# Tesla_Coil_Schematic.net
KiCad netlist of a schematic drawn in Altium Designer
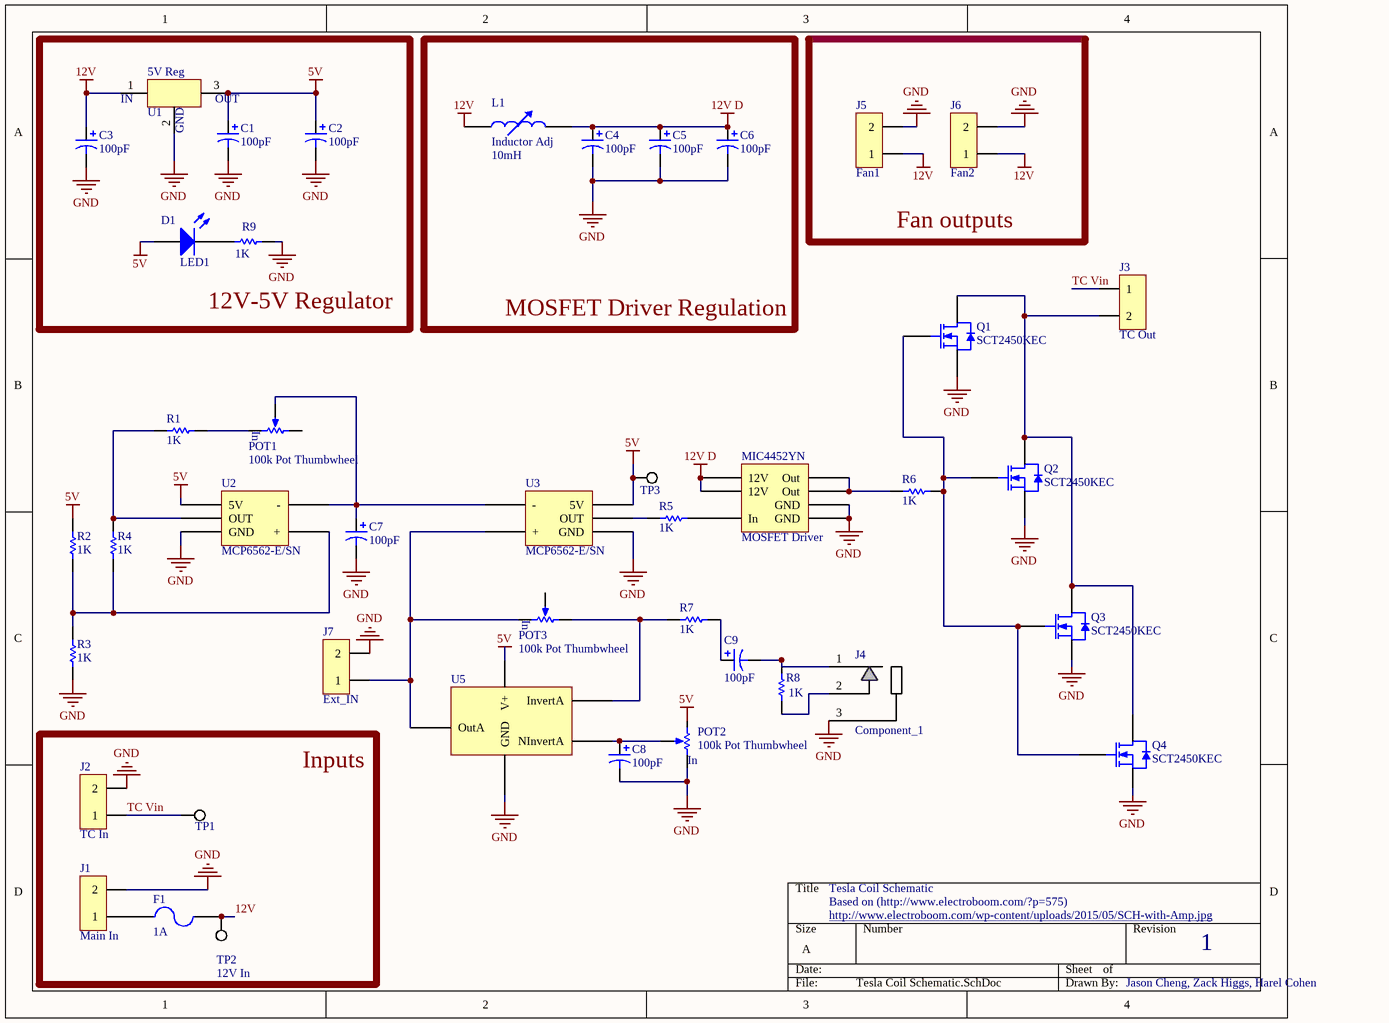
[diagram p0: Tesla Coil Schematic.SchDoc]

(export (version "E")
  (design (tool "Eeschema 10.0.6"))
  (components
    (comp (ref "C1")
      (value "100pF")
      (footprint "CAPPR5-10X30")
      (description "Cap, Gen, 5-10x30")
      (fields (field (name "Comment") "Cap 5-10x30") (field (name "PUBLISHER") "Altium Limited"))
      (libsource (lib "Common") (part "Cap 5-10x30"))
    )
    (comp (ref "C2")
      (value "100pF")
      (footprint "CAPPR5-10X30")
      (description "Cap, Gen, 5-10x30")
      (fields (field (name "Comment") "Cap 5-10x30") (field (name "PUBLISHER") "Altium Limited"))
      (libsource (lib "Common") (part "Cap 5-10x30"))
    )
    (comp (ref "C3")
      (value "100pF")
      (footprint "CAPPR5-10X30")
      (description "Cap, Gen, 5-10x30")
      (fields (field (name "Comment") "Cap 5-10x30") (field (name "PUBLISHER") "Altium Limited"))
      (libsource (lib "Common") (part "Cap 5-10x30"))
    )
    (comp (ref "C4")
      (value "100pF")
      (footprint "CAPPR5-10X30")
      (description "Cap, Gen, 5-10x30")
      (fields (field (name "Comment") "Cap 5-10x30") (field (name "PUBLISHER") "Altium Limited"))
      (libsource (lib "Common") (part "Cap 5-10x30"))
    )
    (comp (ref "C5")
      (value "100pF")
      (footprint "CAPPR5-10X30")
      (description "Cap, Gen, 5-10x30")
      (fields (field (name "Comment") "Cap 5-10x30") (field (name "PUBLISHER") "Altium Limited"))
      (libsource (lib "Common") (part "Cap 5-10x30"))
    )
    (comp (ref "C6")
      (value "100pF")
      (footprint "CAPPR5-10X30")
      (description "Cap, Gen, 5-10x30")
      (fields (field (name "Comment") "Cap 5-10x30") (field (name "PUBLISHER") "Altium Limited"))
      (libsource (lib "Common") (part "Cap 5-10x30"))
    )
    (comp (ref "C7")
      (value "100pF")
      (footprint "CAPPR2-5X11")
      (description "Cap, Gen, 2-5x11")
      (fields (field (name "Comment") "Cap 2-5x11") (field (name "PUBLISHER") "Altium Limited"))
      (libsource (lib "Common") (part "Cap 2-5x11"))
    )
    (comp (ref "C8")
      (value "100pF")
      (footprint "CAPPR2-5X11")
      (description "Cap, Gen, 2-5x11")
      (fields (field (name "Comment") "Cap 2-5x11") (field (name "PUBLISHER") "Altium Limited"))
      (libsource (lib "Common") (part "Cap 2-5x11"))
    )
    (comp (ref "C9")
      (value "100pF")
      (footprint "CAPPR5-10X30")
      (description "Cap, Gen, 5-10x30")
      (fields (field (name "Comment") "Cap 5-10x30") (field (name "PUBLISHER") "Altium Limited"))
      (libsource (lib "Common") (part "Cap 5-10x30"))
    )
    (comp (ref "D1")
      (value "LED1")
      (footprint "LED-1")
      (description "Typical RED GaAs LED")
      (fields (field (name "PUBLISHER") "Altium Limited"))
      (libsource (lib "Miscellaneous Devices") (part "LED1"))
    )
    (comp (ref "F1")
      (value "1A")
      (footprint "Dabs PCB file (1):Blade Fuse")
      (description "Fuse")
      (fields (field (name "PUBLISHER") "Altium Limited"))
      (libsource (lib "Dabs PCB project") (part "Fuse 2"))
    )
    (comp (ref "J1")
      (value "Main In")
      (footprint "Dabs PCB file (1):Mini-Fit Jr. 2")
      (description "Mini-Fit Jr. 2-pin Right Angle")
      (fields
        (field (name "MANUFACTURER") "Molex Inc")
        (field (name "MANUFACTURER PART NUMBER") "0039300020")
      )
      (libsource (lib "Dabs PCB project") (part "Mini-Fit Jr. 2-pin"))
    )
    (comp (ref "J2")
      (value "TC In")
      (footprint "Dabs PCB file (1):Mini-Fit Jr. 2")
      (description "Mini-Fit Jr. 2-pin Right Angle")
      (fields
        (field (name "MANUFACTURER") "Molex Inc")
        (field (name "MANUFACTURER PART NUMBER") "0039300020")
      )
      (libsource (lib "Dabs PCB project") (part "Mini-Fit Jr. 2-pin"))
    )
    (comp (ref "J3")
      (value "TC Out")
      (footprint "Dabs PCB file (1):Mini-Fit Jr. 2")
      (description "Mini-Fit Jr. 2-pin Right Angle")
      (fields
        (field (name "MANUFACTURER") "Molex Inc")
        (field (name "MANUFACTURER PART NUMBER") "0039300020")
      )
      (libsource (lib "") (part "Mini-Fit Jr. 2-pin_1"))
    )
    (comp (ref "J4")
      (value "Component_1")
      (footprint "3.5mm HPJ PCB foot:3.5Jack Foot")
      (libsource (lib "3.5mm HPJ TC") (part "Component_1"))
    )
    (comp (ref "J5")
      (value "Fan1")
      (footprint "Dabs PCB file (1):Mini-Fit Jr. 2")
      (description "Mini-Fit Jr. 2-pin Right Angle")
      (fields
        (field (name "MANUFACTURER") "Molex Inc")
        (field (name "MANUFACTURER PART NUMBER") "0039300020")
      )
      (libsource (lib "Dabs PCB project") (part "Mini-Fit Jr. 2-pin"))
    )
    (comp (ref "J6")
      (value "Fan2")
      (footprint "Dabs PCB file (1):Mini-Fit Jr. 2")
      (description "Mini-Fit Jr. 2-pin Right Angle")
      (fields
        (field (name "MANUFACTURER") "Molex Inc")
        (field (name "MANUFACTURER PART NUMBER") "0039300020")
      )
      (libsource (lib "Dabs PCB project") (part "Mini-Fit Jr. 2-pin"))
    )
    (comp (ref "J7")
      (value "Ext_IN")
      (footprint "Dabs PCB file (1):Mini-Fit Jr. 2")
      (description "Mini-Fit Jr. 2-pin Right Angle")
      (fields
        (field (name "MANUFACTURER") "Molex Inc")
        (field (name "MANUFACTURER PART NUMBER") "0039300020")
      )
      (libsource (lib "Dabs PCB project") (part "Mini-Fit Jr. 2-pin"))
    )
    (comp (ref "L1")
      (value "Inductor Adj")
      (footprint "AXIAL-0.8")
      (description "Adjustable Inductor")
      (fields (field (name "ALTIUM_VALUE") "10mH") (field (name "PUBLISHER") "Altium Limited"))
      (libsource (lib "Miscellaneous Devices") (part "Inductor Adj"))
    )
    (comp (ref "MIC4452YN")
      (value "MOSFET Driver")
      (footprint "MIC441/44")
      (libsource (lib "Tesla_Coil_Parts2") (part "MOSFET Driver"))
    )
    (comp (ref "POT1")
      (value "100k Pot Thumbwheel")
      (footprint "10K Pot 3352T")
      (libsource (lib "Tesla_Coil_Parts2") (part "100k Pot Thumbwheel"))
    )
    (comp (ref "POT2")
      (value "100k Pot Thumbwheel")
      (footprint "10K Pot 3352T")
      (libsource (lib "Tesla_Coil_Parts2") (part "100k Pot Thumbwheel"))
    )
    (comp (ref "POT3")
      (value "100k Pot Thumbwheel")
      (footprint "10K Pot 3352T")
      (libsource (lib "Tesla_Coil_Parts2") (part "100k Pot Thumbwheel"))
    )
    (comp (ref "Q1")
      (value "SCT2450KEC")
      (footprint "SCT2450KEC")
      (libsource (lib "Tesla_Coil_Parts2") (part "SCT2450KEC"))
    )
    (comp (ref "Q2")
      (value "SCT2450KEC")
      (footprint "SCT2450KEC")
      (libsource (lib "Tesla_Coil_Parts2") (part "SCT2450KEC"))
    )
    (comp (ref "Q3")
      (value "SCT2450KEC")
      (footprint "SCT2450KEC")
      (libsource (lib "Tesla_Coil_Parts2") (part "SCT2450KEC"))
    )
    (comp (ref "Q4")
      (value "SCT2450KEC")
      (footprint "SCT2450KEC")
      (libsource (lib "Tesla_Coil_Parts2") (part "SCT2450KEC"))
    )
    (comp (ref "R1")
      (value "1K")
      (footprint "RES10.55-7X2.8")
      (description "R, Gen, Thru Hole")
      (fields (field (name "Comment") "R Thru Hole") (field (name "PUBLISHER") "Altium Limited"))
      (libsource (lib "Common") (part "R Thru Hole"))
    )
    (comp (ref "R2")
      (value "1K")
      (footprint "RES10.55-7X2.8")
      (description "R, Gen, Thru Hole")
      (fields (field (name "Comment") "R Thru Hole") (field (name "PUBLISHER") "Altium Limited"))
      (libsource (lib "Common") (part "R Thru Hole"))
    )
    (comp (ref "R3")
      (value "1K")
      (footprint "RES10.55-7X2.8")
      (description "R, Gen, Thru Hole")
      (fields (field (name "Comment") "R Thru Hole") (field (name "PUBLISHER") "Altium Limited"))
      (libsource (lib "Common") (part "R Thru Hole"))
    )
    (comp (ref "R4")
      (value "1K")
      (footprint "RES10.55-7X2.8")
      (description "R, Gen, Thru Hole")
      (fields (field (name "Comment") "R Thru Hole") (field (name "PUBLISHER") "Altium Limited"))
      (libsource (lib "Common") (part "R Thru Hole"))
    )
    (comp (ref "R5")
      (value "1K")
      (footprint "RES10.55-7X2.8")
      (description "R, Gen, Thru Hole")
      (fields (field (name "Comment") "R Thru Hole") (field (name "PUBLISHER") "Altium Limited"))
      (libsource (lib "Common") (part "R Thru Hole"))
    )
    (comp (ref "R6")
      (value "1K")
      (footprint "RES10.55-7X2.8")
      (description "R, Gen, Thru Hole")
      (fields (field (name "Comment") "R Thru Hole") (field (name "PUBLISHER") "Altium Limited"))
      (libsource (lib "Common") (part "R Thru Hole"))
    )
    (comp (ref "R7")
      (value "1K")
      (footprint "RES10.55-7X2.8")
      (description "R, Gen, Thru Hole")
      (fields (field (name "Comment") "R Thru Hole") (field (name "PUBLISHER") "Altium Limited"))
      (libsource (lib "Common") (part "R Thru Hole"))
    )
    (comp (ref "R8")
      (value "1K")
      (footprint "RES10.55-7X2.8")
      (description "R, Gen, Thru Hole")
      (fields (field (name "Comment") "R Thru Hole") (field (name "PUBLISHER") "Altium Limited"))
      (libsource (lib "Common") (part "R Thru Hole"))
    )
    (comp (ref "R9")
      (value "1K")
      (footprint "RES10.55-7X2.8")
      (description "R, Gen, Thru Hole")
      (fields (field (name "Comment") "R Thru Hole") (field (name "PUBLISHER") "Altium Limited"))
      (libsource (lib "Common") (part "R Thru Hole"))
    )
    (comp (ref "TP1")
      (value "Test Point")
      (footprint "Dabs PCB file (1):Test Point")
      (libsource (lib "Dabs PCB project") (part "Test Point"))
    )
    (comp (ref "TP2")
      (value "Test Point")
      (footprint "Dabs PCB file (1):Test Point")
      (fields (field (name "LABEL") "12V In"))
      (libsource (lib "Dabs PCB project") (part "Test Point"))
    )
    (comp (ref "TP3")
      (value "Test Point")
      (footprint "Dabs PCB file (1):Test Point")
      (libsource (lib "Dabs PCB project") (part "Test Point"))
    )
    (comp (ref "U1") (value "REG") (footprint "5V REG") (libsource (lib "Tesla_Coil_Parts2") (part "REG")))
    (comp (ref "U2")
      (value "MCP6562-E/SN")
      (footprint "MCP6562")
      (libsource (lib "Tesla_Coil_Parts") (part "MCP6562-E/SN"))
    )
    (comp (ref "U3")
      (value "MCP6562-E/SN")
      (footprint "MCP6562")
      (libsource (lib "Tesla_Coil_Parts2") (part "MCP6562-E/SN"))
    )
    (comp (ref "U5")
      (value "LM358 (DIP Socket)")
      (footprint "3M5473-ND-")
      (libsource (lib "Tesla_Coil_Parts2") (part "LM358 (DIP Socket)"))
    )
  )
  (nets
    (net (code "1") (name "/TC Vin") (class "Default")
      (node (ref "J2") (pin "1") (pinfunction "1_1") (pintype "passive"))
      (node (ref "J3") (pin "1") (pinfunction "1_1") (pintype "passive"))
      (node (ref "TP1") (pin "1") (pinfunction "1_1") (pintype "passive"))
    )
    (net (code "2") (name "5V") (class "Default")
      (node (ref "C1") (pin "1") (pinfunction "1_1") (pintype "passive"))
      (node (ref "C2") (pin "1") (pinfunction "1_1") (pintype "passive"))
      (node (ref "D1") (pin "1") (pinfunction "A_1") (pintype "passive"))
      (node (ref "R2") (pin "2") (pinfunction "2_2") (pintype "passive"))
      (node (ref "TP3") (pin "1") (pinfunction "1_1") (pintype "passive"))
      (node (ref "U1") (pin "3") (pintype "passive"))
      (node (ref "U2") (pin "5") (pinfunction "5V_5") (pintype "passive"))
      (node (ref "U3") (pin "8") (pinfunction "5V_8") (pintype "passive"))
      (node (ref "U5") (pin "8") (pinfunction "V+_8") (pintype "passive"))
    )
    (net (code "3") (name "12V") (class "Default")
      (node (ref "C3") (pin "1") (pinfunction "1_1") (pintype "passive"))
      (node (ref "F1") (pin "2") (pinfunction "2_2") (pintype "passive"))
      (node (ref "J5") (pin "1") (pinfunction "1_1") (pintype "passive"))
      (node (ref "J6") (pin "1") (pinfunction "1_1") (pintype "passive"))
      (node (ref "L1") (pin "1") (pinfunction "1_1") (pintype "passive"))
      (node (ref "TP2") (pin "1") (pinfunction "1_1") (pintype "passive"))
      (node (ref "U1") (pin "1") (pintype "passive"))
    )
    (net (code "4") (name "12V D") (class "Default")
      (node (ref "C4") (pin "1") (pinfunction "1_1") (pintype "passive"))
      (node (ref "C5") (pin "1") (pinfunction "1_1") (pintype "passive"))
      (node (ref "C6") (pin "1") (pinfunction "1_1") (pintype "passive"))
      (node (ref "L1") (pin "2") (pinfunction "2_2") (pintype "passive"))
      (node (ref "MIC4452YN") (pin "1") (pinfunction "12V_1") (pintype "passive"))
      (node (ref "MIC4452YN") (pin "8") (pinfunction "12V_8") (pintype "passive"))
    )
    (net (code "5") (name "GND") (class "Default")
      (node (ref "C1") (pin "2") (pinfunction "2_2") (pintype "passive"))
      (node (ref "C2") (pin "2") (pinfunction "2_2") (pintype "passive"))
      (node (ref "C3") (pin "2") (pinfunction "2_2") (pintype "passive"))
      (node (ref "C4") (pin "2") (pinfunction "2_2") (pintype "passive"))
      (node (ref "C5") (pin "2") (pinfunction "2_2") (pintype "passive"))
      (node (ref "C6") (pin "2") (pinfunction "2_2") (pintype "passive"))
      (node (ref "C7") (pin "2") (pinfunction "2_2") (pintype "passive"))
      (node (ref "C8") (pin "2") (pinfunction "2_2") (pintype "passive"))
      (node (ref "J1") (pin "2") (pinfunction "2_2") (pintype "passive"))
      (node (ref "J2") (pin "2") (pinfunction "2_2") (pintype "passive"))
      (node (ref "J4") (pin "3") (pinfunction "3_3") (pintype "passive"))
      (node (ref "J5") (pin "2") (pinfunction "2_2") (pintype "passive"))
      (node (ref "J6") (pin "2") (pinfunction "2_2") (pintype "passive"))
      (node (ref "J7") (pin "2") (pinfunction "2_2") (pintype "passive"))
      (node (ref "MIC4452YN") (pin "5") (pinfunction "GND_5") (pintype "passive"))
      (node (ref "MIC4452YN") (pin "6") (pinfunction "GND_6") (pintype "passive"))
      (node (ref "POT2") (pin "1") (pinfunction "In_1") (pintype "passive"))
      (node (ref "Q1") (pin "3") (pinfunction "3_3") (pintype "passive"))
      (node (ref "Q2") (pin "3") (pinfunction "3_3") (pintype "passive"))
      (node (ref "Q3") (pin "3") (pinfunction "3_3") (pintype "passive"))
      (node (ref "Q4") (pin "3") (pinfunction "3_3") (pintype "passive"))
      (node (ref "R3") (pin "1") (pinfunction "1_1") (pintype "passive"))
      (node (ref "R9") (pin "1") (pinfunction "1_1") (pintype "passive"))
      (node (ref "U1") (pin "2") (pintype "passive"))
      (node (ref "U2") (pin "2") (pinfunction "GND_2") (pintype "passive"))
      (node (ref "U3") (pin "4") (pinfunction "GND_4") (pintype "passive"))
      (node (ref "U5") (pin "4") (pinfunction "GND_4") (pintype "passive"))
    )
    (net (code "6") (name "Net-(C9-Pad1)") (class "Default")
      (node (ref "C9") (pin "1") (pinfunction "1_1") (pintype "passive"))
      (node (ref "R7") (pin "2") (pinfunction "2_2") (pintype "passive"))
    )
    (net (code "7") (name "Net-(C9-Pad2)") (class "Default")
      (node (ref "C9") (pin "2") (pinfunction "2_2") (pintype "passive"))
      (node (ref "J4") (pin "1") (pinfunction "1_1") (pintype "passive"))
      (node (ref "R8") (pin "2") (pinfunction "2_2") (pintype "passive"))
    )
    (net (code "8") (name "Net-(D1-K)") (class "Default")
      (node (ref "D1") (pin "2") (pinfunction "K_2") (pintype "passive"))
      (node (ref "R9") (pin "2") (pinfunction "2_2") (pintype "passive"))
    )
    (net (code "9") (name "Net-(F1-Pad1)") (class "Default")
      (node (ref "F1") (pin "1") (pinfunction "1_1") (pintype "passive"))
      (node (ref "J1") (pin "1") (pinfunction "1_1") (pintype "passive"))
    )
    (net (code "10") (name "Net-(J3-Pad2)") (class "Default")
      (node (ref "J3") (pin "2") (pinfunction "2_2") (pintype "passive"))
      (node (ref "Q1") (pin "2") (pinfunction "2_2") (pintype "passive"))
      (node (ref "Q2") (pin "2") (pinfunction "2_2") (pintype "passive"))
      (node (ref "Q3") (pin "2") (pinfunction "2_2") (pintype "passive"))
      (node (ref "Q4") (pin "2") (pinfunction "2_2") (pintype "passive"))
    )
    (net (code "11") (name "Net-(J4-Pad2)") (class "Default")
      (node (ref "J4") (pin "2") (pinfunction "2_2") (pintype "passive"))
      (node (ref "R8") (pin "1") (pinfunction "1_1") (pintype "passive"))
    )
    (net (code "12") (name "Net-(MIC4452YN-In)") (class "Default")
      (node (ref "MIC4452YN") (pin "2") (pinfunction "In_2") (pintype "passive"))
      (node (ref "R5") (pin "2") (pinfunction "2_2") (pintype "passive"))
    )
    (net (code "13") (name "Net-(MIC4452YN-Out-Pad6)") (class "Default")
      (node (ref "MIC4452YN") (pin "6") (pinfunction "Out_6") (pintype "passive"))
      (node (ref "MIC4452YN") (pin "7") (pinfunction "Out_7") (pintype "passive"))
      (node (ref "R6") (pin "1") (pinfunction "1_1") (pintype "passive"))
    )
    (net (code "14") (name "Net-(POT1-In)") (class "Default")
      (node (ref "POT1") (pin "1") (pinfunction "In_1") (pintype "passive"))
      (node (ref "R1") (pin "2") (pinfunction "2_2") (pintype "passive"))
    )
    (net (code "15") (name "Net-(POT1-TAP)") (class "Default")
      (node (ref "C7") (pin "1") (pinfunction "1_1") (pintype "passive"))
      (node (ref "POT1") (pin "2") (pinfunction "TAP_2") (pintype "passive"))
      (node (ref "U2") (pin "4") (pinfunction "-_4") (pintype "passive"))
      (node (ref "U3") (pin "2") (pinfunction "-_2") (pintype "passive"))
    )
    (net (code "16") (name "Net-(POT2-TAP)") (class "Default")
      (node (ref "C8") (pin "1") (pinfunction "1_1") (pintype "passive"))
      (node (ref "POT2") (pin "2") (pinfunction "TAP_2") (pintype "passive"))
      (node (ref "U5") (pin "3") (pinfunction "NInvertA_3") (pintype "passive"))
    )
    (net (code "17") (name "Net-(POT3-In)") (class "Default")
      (node (ref "J7") (pin "1") (pinfunction "1_1") (pintype "passive"))
      (node (ref "POT3") (pin "1") (pinfunction "In_1") (pintype "passive"))
      (node (ref "U3") (pin "3") (pinfunction "+_3") (pintype "passive"))
      (node (ref "U5") (pin "1") (pinfunction "OutA_1") (pintype "passive"))
    )
    (net (code "18") (name "Net-(POT3-TOP)") (class "Default")
      (node (ref "POT3") (pin "3") (pinfunction "TOP_3") (pintype "passive"))
      (node (ref "R7") (pin "1") (pinfunction "1_1") (pintype "passive"))
      (node (ref "U5") (pin "2") (pinfunction "InvertA_2") (pintype "passive"))
    )
    (net (code "19") (name "Net-(Q1-Pad1)") (class "Default")
      (node (ref "Q1") (pin "1") (pinfunction "1_1") (pintype "passive"))
      (node (ref "Q2") (pin "1") (pinfunction "1_1") (pintype "passive"))
      (node (ref "Q3") (pin "1") (pinfunction "1_1") (pintype "passive"))
      (node (ref "Q4") (pin "1") (pinfunction "1_1") (pintype "passive"))
      (node (ref "R6") (pin "2") (pinfunction "2_2") (pintype "passive"))
    )
    (net (code "20") (name "Net-(U2-+)") (class "Default")
      (node (ref "R2") (pin "1") (pinfunction "1_1") (pintype "passive"))
      (node (ref "R3") (pin "2") (pinfunction "2_2") (pintype "passive"))
      (node (ref "R4") (pin "1") (pinfunction "1_1") (pintype "passive"))
      (node (ref "U2") (pin "3") (pinfunction "+_3") (pintype "passive"))
    )
    (net (code "21") (name "Net-(U2-OUT)") (class "Default")
      (node (ref "R1") (pin "1") (pinfunction "1_1") (pintype "passive"))
      (node (ref "R4") (pin "2") (pinfunction "2_2") (pintype "passive"))
      (node (ref "U2") (pin "1") (pinfunction "OUT_1") (pintype "passive"))
    )
    (net (code "22") (name "Net-(U3-OUT)") (class "Default")
      (node (ref "R5") (pin "1") (pinfunction "1_1") (pintype "passive"))
      (node (ref "U3") (pin "1") (pinfunction "OUT_1") (pintype "passive"))
    )
    (net (code "23") (name "unconnected-(POT1-TOP-Pad3)") (class "Default")
      (node (ref "POT1") (pin "3") (pinfunction "TOP_3") (pintype "passive"))
    )
    (net (code "24") (name "unconnected-(POT2-TOP-Pad3)") (class "Default")
      (node (ref "POT2") (pin "3") (pinfunction "TOP_3") (pintype "passive"))
    )
    (net (code "25") (name "unconnected-(POT3-TAP-Pad2)") (class "Default")
      (node (ref "POT3") (pin "2") (pinfunction "TAP_2") (pintype "passive"))
    )
  )
)
